# 7805.net
KiCad netlist of a schematic drawn in Altium Designer
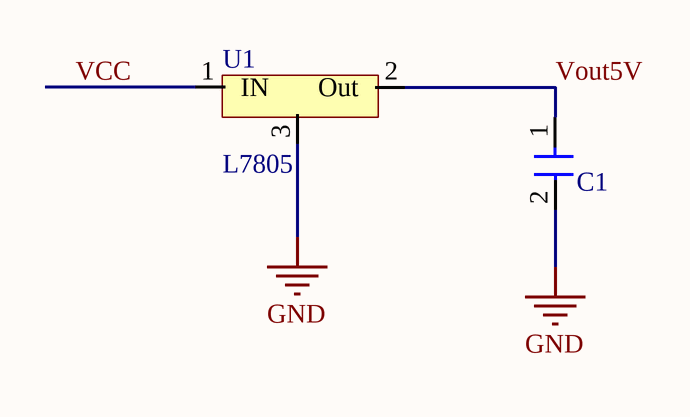
[diagram p0: 7805.SchDoc]

(export (version "E")
  (design (tool "Eeschema 10.0.6"))
  (components
    (comp (ref "C1")
      (value "Cap")
      (footprint "Cap1")
      (description "CAP FILM 0.1UF 63VDC RADIAL")
      (fields
        (field (name "MANUFACTURER") "Kemet")
        (field (name "MANUFACTURER PART NUMBER") "R82DC3100DQ50J")
      )
      (libsource (lib "EgitimPowerSupply") (part "R82DC3100DQ50J"))
    )
    (comp (ref "U1")
      (value "L7805")
      (footprint "TO220")
      (description "Linear Voltage Regulators 5.0V 1.0A Positive")
      (fields
        (field (name "MANUFACTURER") "STMicroelectronics")
        (field (name "MANUFACTURER PART NUMBER") "L7805ACV")
      )
      (libsource (lib "EgitimPowerSupply") (part "L7805ACV"))
    )
  )
  (nets
    (net (code "1") (name "/VCC") (class "Default")
      (node (ref "U1") (pin "1") (pinfunction "IN_1") (pintype "passive"))
    )
    (net (code "2") (name "/Vout5V") (class "Default")
      (node (ref "C1") (pin "1") (pinfunction "1_1") (pintype "passive"))
      (node (ref "U1") (pin "2") (pinfunction "Out_2") (pintype "passive"))
    )
    (net (code "3") (name "GND") (class "Default")
      (node (ref "C1") (pin "2") (pinfunction "2_2") (pintype "passive"))
      (node (ref "U1") (pin "3") (pinfunction "3_3") (pintype "passive"))
    )
  )
)
